# 05_NOT.net
KiCad netlist of a schematic drawn in EAGLE
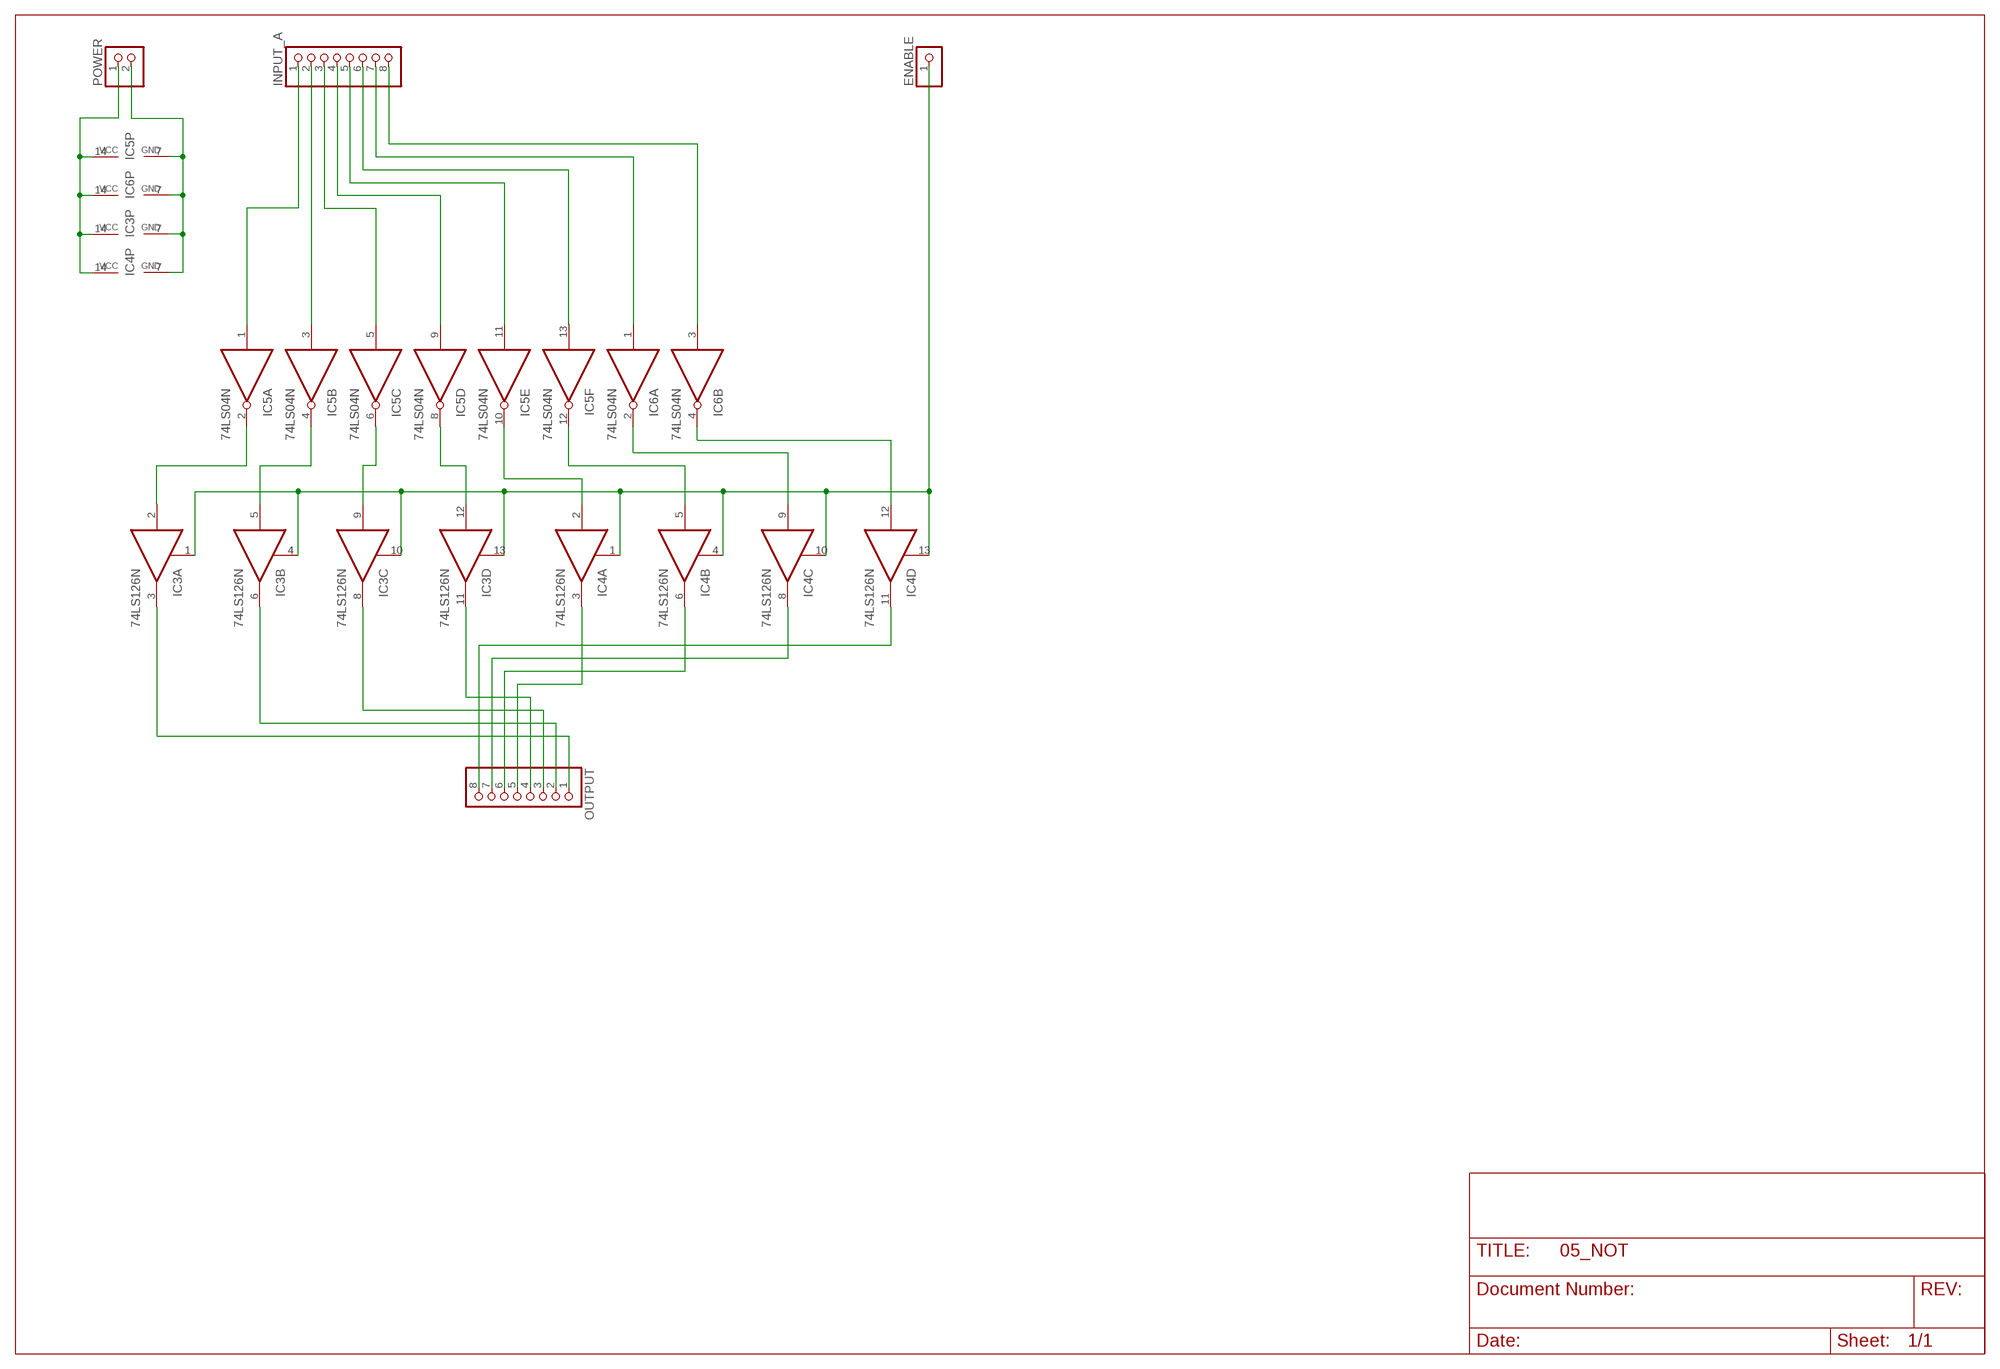
[diagram p0: schematic, sheet 1]

(export (version "E")
  (design (tool "Eeschema 10.0.6"))
  (components
    (comp (ref "ENABLE")
      (value "PINHD-1X1")
      (footprint "eagle-import:1X01")
      (libsource (lib "eagle-import") (part "PINHD-1X1"))
    )
    (comp (ref "IC3")
      (value "74LS126N")
      (footprint "eagle-import:DIL14")
      (libsource (lib "eagle-import") (part "74126NLS"))
    )
    (comp (ref "IC4")
      (value "74LS126N")
      (footprint "eagle-import:DIL14")
      (libsource (lib "eagle-import") (part "74126NLS"))
    )
    (comp (ref "IC5")
      (value "74LS04N")
      (footprint "eagle-import:DIL14")
      (libsource (lib "eagle-import") (part "7404NLS"))
    )
    (comp (ref "IC6")
      (value "74LS04N")
      (footprint "eagle-import:DIL14")
      (libsource (lib "eagle-import") (part "7404NLS"))
    )
    (comp (ref "INPUT_A")
      (value "PINHD-1X8")
      (footprint "eagle-import:1X08")
      (libsource (lib "eagle-import") (part "PINHD-1X8"))
    )
    (comp (ref "OUTPUT")
      (value "PINHD-1X8")
      (footprint "eagle-import:1X08")
      (libsource (lib "eagle-import") (part "PINHD-1X8"))
    )
    (comp (ref "POWER")
      (value "PINHD-1X2")
      (footprint "eagle-import:1X02")
      (libsource (lib "eagle-import") (part "PINHD-1X2"))
    )
  )
  (nets
    (net (code "1") (name "Net-(IC3A-I)") (class "Default")
      (node (ref "IC3") (pin "2") (pinfunction "I_2") (pintype "input"))
      (node (ref "IC5") (pin "2") (pinfunction "O_2") (pintype "output"))
    )
    (net (code "2") (name "Net-(IC3A-O)") (class "Default")
      (node (ref "IC3") (pin "3") (pinfunction "O_3") (pintype "output"))
      (node (ref "OUTPUT") (pin "1") (pinfunction "1_1") (pintype "passive"))
    )
    (net (code "3") (name "Net-(IC3A-OE)") (class "Default")
      (node (ref "ENABLE") (pin "1") (pinfunction "1_1") (pintype "passive"))
      (node (ref "IC3") (pin "1") (pinfunction "OE_1") (pintype "input"))
      (node (ref "IC3") (pin "10") (pinfunction "OE_10") (pintype "input"))
      (node (ref "IC3") (pin "13") (pinfunction "OE_13") (pintype "input"))
      (node (ref "IC3") (pin "4") (pinfunction "OE_4") (pintype "input"))
      (node (ref "IC4") (pin "1") (pinfunction "OE_1") (pintype "input"))
      (node (ref "IC4") (pin "10") (pinfunction "OE_10") (pintype "input"))
      (node (ref "IC4") (pin "13") (pinfunction "OE_13") (pintype "input"))
      (node (ref "IC4") (pin "4") (pinfunction "OE_4") (pintype "input"))
    )
    (net (code "4") (name "Net-(IC3B-I)") (class "Default")
      (node (ref "IC3") (pin "5") (pinfunction "I_5") (pintype "input"))
      (node (ref "IC5") (pin "4") (pinfunction "O_4") (pintype "output"))
    )
    (net (code "5") (name "Net-(IC3B-O)") (class "Default")
      (node (ref "IC3") (pin "6") (pinfunction "O_6") (pintype "output"))
      (node (ref "OUTPUT") (pin "2") (pinfunction "2_2") (pintype "passive"))
    )
    (net (code "6") (name "Net-(IC3C-I)") (class "Default")
      (node (ref "IC3") (pin "9") (pinfunction "I_9") (pintype "input"))
      (node (ref "IC5") (pin "6") (pinfunction "O_6") (pintype "output"))
    )
    (net (code "7") (name "Net-(IC3C-O)") (class "Default")
      (node (ref "IC3") (pin "8") (pinfunction "O_8") (pintype "output"))
      (node (ref "OUTPUT") (pin "3") (pinfunction "3_3") (pintype "passive"))
    )
    (net (code "8") (name "Net-(IC3D-I)") (class "Default")
      (node (ref "IC3") (pin "12") (pinfunction "I_12") (pintype "input"))
      (node (ref "IC5") (pin "8") (pinfunction "O_8") (pintype "output"))
    )
    (net (code "9") (name "Net-(IC3D-O)") (class "Default")
      (node (ref "IC3") (pin "11") (pinfunction "O_11") (pintype "output"))
      (node (ref "OUTPUT") (pin "4") (pinfunction "4_4") (pintype "passive"))
    )
    (net (code "10") (name "Net-(IC3E-GND)") (class "Default")
      (node (ref "IC3") (pin "7") (pinfunction "GND_7") (pintype "power_in"))
      (node (ref "IC4") (pin "7") (pinfunction "GND_7") (pintype "power_in"))
      (node (ref "IC5") (pin "7") (pinfunction "GND_7") (pintype "power_in"))
      (node (ref "IC6") (pin "7") (pinfunction "GND_7") (pintype "power_in"))
      (node (ref "POWER") (pin "2") (pinfunction "2_2") (pintype "passive"))
    )
    (net (code "11") (name "Net-(IC3E-VCC)") (class "Default")
      (node (ref "IC3") (pin "14") (pinfunction "VCC_14") (pintype "power_in"))
      (node (ref "IC4") (pin "14") (pinfunction "VCC_14") (pintype "power_in"))
      (node (ref "IC5") (pin "14") (pinfunction "VCC_14") (pintype "power_in"))
      (node (ref "IC6") (pin "14") (pinfunction "VCC_14") (pintype "power_in"))
      (node (ref "POWER") (pin "1") (pinfunction "1_1") (pintype "passive"))
    )
    (net (code "12") (name "Net-(IC4A-I)") (class "Default")
      (node (ref "IC4") (pin "2") (pinfunction "I_2") (pintype "input"))
      (node (ref "IC5") (pin "10") (pinfunction "O_10") (pintype "output"))
    )
    (net (code "13") (name "Net-(IC4A-O)") (class "Default")
      (node (ref "IC4") (pin "3") (pinfunction "O_3") (pintype "output"))
      (node (ref "OUTPUT") (pin "5") (pinfunction "5_5") (pintype "passive"))
    )
    (net (code "14") (name "Net-(IC4B-I)") (class "Default")
      (node (ref "IC4") (pin "5") (pinfunction "I_5") (pintype "input"))
      (node (ref "IC5") (pin "12") (pinfunction "O_12") (pintype "output"))
    )
    (net (code "15") (name "Net-(IC4B-O)") (class "Default")
      (node (ref "IC4") (pin "6") (pinfunction "O_6") (pintype "output"))
      (node (ref "OUTPUT") (pin "6") (pinfunction "6_6") (pintype "passive"))
    )
    (net (code "16") (name "Net-(IC4C-I)") (class "Default")
      (node (ref "IC4") (pin "9") (pinfunction "I_9") (pintype "input"))
      (node (ref "IC6") (pin "2") (pinfunction "O_2") (pintype "output"))
    )
    (net (code "17") (name "Net-(IC4C-O)") (class "Default")
      (node (ref "IC4") (pin "8") (pinfunction "O_8") (pintype "output"))
      (node (ref "OUTPUT") (pin "7") (pinfunction "7_7") (pintype "passive"))
    )
    (net (code "18") (name "Net-(IC4D-I)") (class "Default")
      (node (ref "IC4") (pin "12") (pinfunction "I_12") (pintype "input"))
      (node (ref "IC6") (pin "4") (pinfunction "O_4") (pintype "output"))
    )
    (net (code "19") (name "Net-(IC4D-O)") (class "Default")
      (node (ref "IC4") (pin "11") (pinfunction "O_11") (pintype "output"))
      (node (ref "OUTPUT") (pin "8") (pinfunction "8_8") (pintype "passive"))
    )
    (net (code "20") (name "Net-(IC5A-I)") (class "Default")
      (node (ref "IC5") (pin "1") (pinfunction "I_1") (pintype "input"))
      (node (ref "INPUT_A") (pin "1") (pinfunction "1_1") (pintype "passive"))
    )
    (net (code "21") (name "Net-(IC5B-I)") (class "Default")
      (node (ref "IC5") (pin "3") (pinfunction "I_3") (pintype "input"))
      (node (ref "INPUT_A") (pin "2") (pinfunction "2_2") (pintype "passive"))
    )
    (net (code "22") (name "Net-(IC5C-I)") (class "Default")
      (node (ref "IC5") (pin "5") (pinfunction "I_5") (pintype "input"))
      (node (ref "INPUT_A") (pin "3") (pinfunction "3_3") (pintype "passive"))
    )
    (net (code "23") (name "Net-(IC5D-I)") (class "Default")
      (node (ref "IC5") (pin "9") (pinfunction "I_9") (pintype "input"))
      (node (ref "INPUT_A") (pin "4") (pinfunction "4_4") (pintype "passive"))
    )
    (net (code "24") (name "Net-(IC5E-I)") (class "Default")
      (node (ref "IC5") (pin "11") (pinfunction "I_11") (pintype "input"))
      (node (ref "INPUT_A") (pin "5") (pinfunction "5_5") (pintype "passive"))
    )
    (net (code "25") (name "Net-(IC5F-I)") (class "Default")
      (node (ref "IC5") (pin "13") (pinfunction "I_13") (pintype "input"))
      (node (ref "INPUT_A") (pin "6") (pinfunction "6_6") (pintype "passive"))
    )
    (net (code "26") (name "Net-(IC6A-I)") (class "Default")
      (node (ref "IC6") (pin "1") (pinfunction "I_1") (pintype "input"))
      (node (ref "INPUT_A") (pin "7") (pinfunction "7_7") (pintype "passive"))
    )
    (net (code "27") (name "Net-(IC6B-I)") (class "Default")
      (node (ref "IC6") (pin "3") (pinfunction "I_3") (pintype "input"))
      (node (ref "INPUT_A") (pin "8") (pinfunction "8_8") (pintype "passive"))
    )
  )
)
